# MAIN.net
KiCad netlist of a schematic drawn in Altium Designer
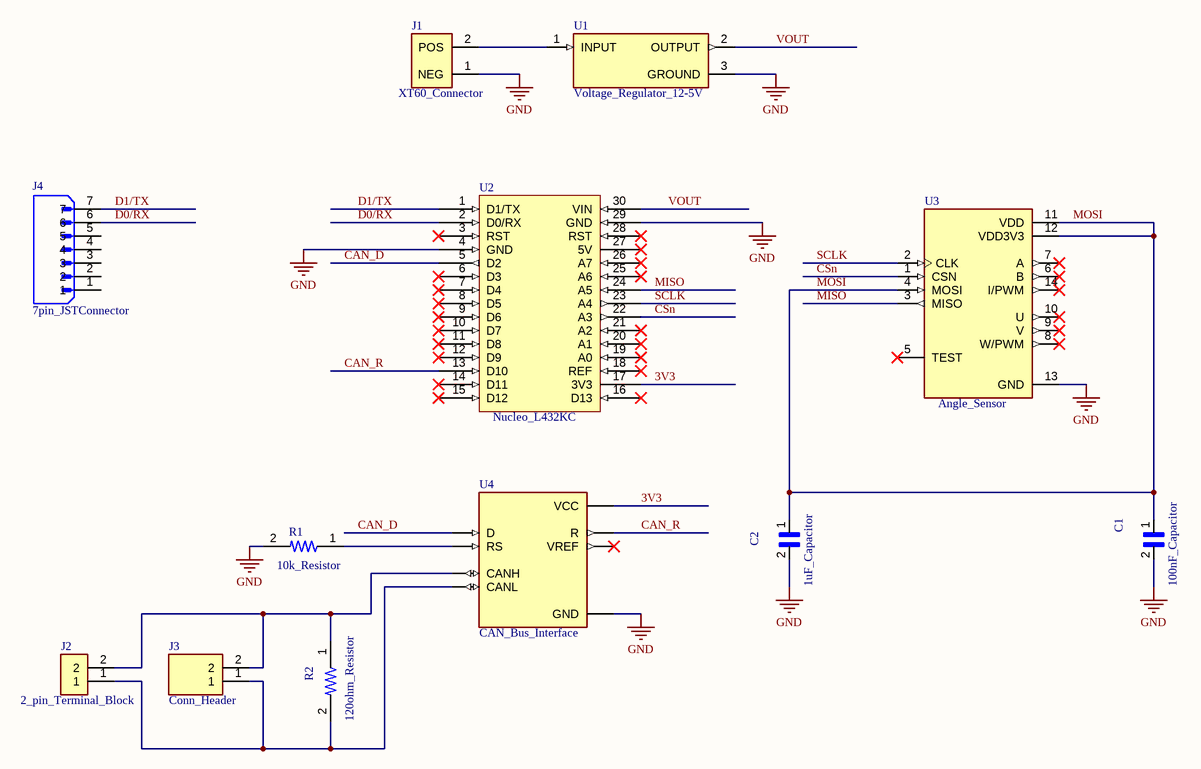
[diagram p0: MAIN.SchDoc]

(export (version "E")
  (design (tool "Eeschema 10.0.6"))
  (components
    (comp (ref "C1")
      (value "100nF_Capacitor")
      (footprint "100nF_Capacitor")
      (description "Multilayer Ceramic Capacitors MLCC - SMD/SMT 100nF 25volts 10%")
      (fields
        (field (name "MANUFACTURER") "Vishay Vitramon")
        (field (name "MANUFACTURER PART NUMBER") "VJ0603Y104KLXAC5G")
      )
      (libsource (lib "Sch_Lib") (part "100nF_Capacitor"))
    )
    (comp (ref "C2")
      (value "1uF_Capacitor")
      (footprint "1uF_Capacitor")
      (description "Multilayer Ceramic Capacitors MLCC - SMD/SMT 1uF 50V 0603 RoHS")
      (fields
        (field (name "MANUFACTURER") "Yageo")
        (field (name "MANUFACTURER PART NUMBER") "CC0603KRX5R9BB105")
      )
      (libsource (lib "Sch_Lib") (part "1uF_Capacitor"))
    )
    (comp (ref "J1")
      (value "XT60_Connector")
      (footprint "XT60_Connector")
      (description "20.5x8.1mm 铜镀金 DC500V 30A")
      (fields (field (name "MANUFACTURER") "Amass") (field (name "MANUFACTURER PART NUMBER") "XT60-M"))
      (libsource (lib "Sch_Lib") (part "XT60_Connector"))
    )
    (comp (ref "J2")
      (value "2_pin_Terminal_Block")
      (footprint "Terminal_Block")
      (description "Connector, Terminal Block; Wire Receptacle; 2 Pos.; 16-30 AWG; 0.2 in. CL; Side;")
      (fields
        (field (name "MANUFACTURER") "TE Connectivity")
        (field (name "MANUFACTURER PART NUMBER") "282837-2")
      )
      (libsource (lib "Sch_Lib") (part "2_pin_Terminal_Block"))
    )
    (comp (ref "J3")
      (value "Conn_Header")
      (footprint "Conn_Header")
      (description "Conn Unshrouded Header HDR 2 POS 2.54mm Solder ST Thru-Hole Automotive Carton")
      (fields
        (field (name "MANUFACTURER") "TE Connectivity")
        (field (name "MANUFACTURER PART NUMBER") "826629-2")
      )
      (libsource (lib "Sch_Lib") (part "Conn_Header"))
    )
    (comp (ref "J4")
      (value "7pin_JSTConnector")
      (footprint "7pin_JSTConnector")
      (description "Connector Header, XH Series, 7 Position, 2.50mm, Through Hole, Press-Fit, Solder, Natural")
      (fields
        (field (name "MANUFACTURER") "JST")
        (field (name "MANUFACTURER PART NUMBER") "B7B-XH-A(LF)(SN)")
      )
      (libsource (lib "Sch_Lib") (part "7pin_JSTConnector"))
    )
    (comp (ref "R1")
      (value "10k_Resistor")
      (footprint "10k_Resistor")
      (description "Res Thin Film 0603 10K Ohm 0.1% 0.167W ±25ppm/C Epoxy Pad SMD T/R")
      (fields
        (field (name "MANUFACTURER") "TE Connectivity")
        (field (name "MANUFACTURER PART NUMBER") "RP73PF1J10KBTDF")
      )
      (libsource (lib "Sch_Lib") (part "10k_Resistor"))
    )
    (comp (ref "R2")
      (value "120ohm_Resistor")
      (footprint "120ohm_Resistor")
      (description "Res Thick Film 0603 120 Ohm 1% 1/10W ±100ppm/°C Molded SMD SMD Paper T/R")
      (fields
        (field (name "MANUFACTURER") "Yageo")
        (field (name "MANUFACTURER PART NUMBER") "RC0603FR-10120RL")
      )
      (libsource (lib "Sch_Lib") (part "120ohm_Resistor"))
    )
    (comp (ref "U1")
      (value "Voltage_Regulator_12-5V")
      (footprint "Voltage_Regulator_12-5V")
      (description "IC REG LDO 5V 1.5A DPAK")
      (fields
        (field (name "MANUFACTURER") "STMicroelectronics")
        (field (name "MANUFACTURER PART NUMBER") "L7805CDT-TR")
      )
      (libsource (lib "Sch_Lib") (part "Voltage_Regulator_12-5V"))
    )
    (comp (ref "U2")
      (value "Nucleo_L432KC")
      (footprint "Nucleo_L432KC")
      (description "STM32 Nucleo-32 development board with STM32L432KC MCU, supports Arduino connectivity")
      (fields
        (field (name "MANUFACTURER") "STMicroelectronics")
        (field (name "MANUFACTURER PART NUMBER") "NUCLEO-L432KC")
      )
      (libsource (lib "Sch_Lib") (part "Nucleo_L432KC"))
    )
    (comp (ref "U3")
      (value "Angle_Sensor")
      (footprint "Angle_Sensor_AS5047P")
      (description "AS5047P Series 5.5 V 14-bit On-Axis Magnetic Rotary Position Sensor - TSSOP-14")
      (fields (field (name "MANUFACTURER") "ams") (field (name "MANUFACTURER PART NUMBER") "AS5047P-ATSM"))
      (libsource (lib "Sch_Lib") (part "Angle_Sensor"))
    )
    (comp (ref "U4")
      (value "CAN_Bus_Interface")
      (footprint "CAN_Bus_Interface")
      (fields
        (field (name "MANUFACTURER") "Texas Instruments")
        (field (name "MANUFACTURER PART NUMBER") "SN65HVD230")
      )
      (libsource (lib "Sch_Lib") (part "CAN_Bus_Interface"))
    )
  )
  (nets
    (net (code "1") (name "/3V3") (class "Default")
      (node (ref "U2") (pin "17") (pinfunction "3V3_17") (pintype "power_in"))
      (node (ref "U4") (pin "3") (pinfunction "VCC_3") (pintype "power_in"))
    )
    (net (code "2") (name "/CAN_D") (class "Default")
      (node (ref "U2") (pin "5") (pinfunction "D2_5") (pintype "output"))
      (node (ref "U4") (pin "1") (pinfunction "D_1") (pintype "input"))
    )
    (net (code "3") (name "/CAN_R") (class "Default")
      (node (ref "U2") (pin "13") (pinfunction "D10_13") (pintype "input"))
      (node (ref "U4") (pin "4") (pinfunction "R_4") (pintype "output"))
    )
    (net (code "4") (name "/CSn") (class "Default")
      (node (ref "U2") (pin "22") (pinfunction "A3_22") (pintype "output"))
      (node (ref "U3") (pin "1") (pinfunction "CSN_1") (pintype "input"))
    )
    (net (code "5") (name "/D0{slash}RX") (class "Default")
      (node (ref "J4") (pin "6") (pinfunction "6_6") (pintype "passive"))
      (node (ref "U2") (pin "2") (pinfunction "D0/RX_2") (pintype "input"))
    )
    (net (code "6") (name "/D1{slash}TX") (class "Default")
      (node (ref "J4") (pin "7") (pinfunction "7_7") (pintype "passive"))
      (node (ref "U2") (pin "1") (pinfunction "D1/TX_1") (pintype "input"))
    )
    (net (code "7") (name "/MISO") (class "Default")
      (node (ref "U2") (pin "24") (pinfunction "A5_24") (pintype "input"))
      (node (ref "U3") (pin "3") (pinfunction "MISO_3") (pintype "output"))
    )
    (net (code "8") (name "/MOSI") (class "Default")
      (node (ref "C1") (pin "1") (pinfunction "1_1") (pintype "passive"))
      (node (ref "C2") (pin "1") (pinfunction "1_1") (pintype "passive"))
      (node (ref "U3") (pin "11") (pinfunction "VDD_11") (pintype "power_in"))
      (node (ref "U3") (pin "12") (pinfunction "VDD3V3_12") (pintype "power_in"))
      (node (ref "U3") (pin "4") (pinfunction "MOSI_4") (pintype "input"))
    )
    (net (code "9") (name "/SCLK") (class "Default")
      (node (ref "U2") (pin "23") (pinfunction "A4_23") (pintype "output"))
      (node (ref "U3") (pin "2") (pinfunction "CLK_2") (pintype "input"))
    )
    (net (code "10") (name "/VOUT") (class "Default")
      (node (ref "U1") (pin "2") (pinfunction "OUTPUT_2") (pintype "output"))
      (node (ref "U2") (pin "30") (pinfunction "VIN_30") (pintype "input"))
    )
    (net (code "11") (name "GND") (class "Default")
      (node (ref "C1") (pin "2") (pinfunction "2_2") (pintype "passive"))
      (node (ref "C2") (pin "2") (pinfunction "2_2") (pintype "passive"))
      (node (ref "J1") (pin "1") (pinfunction "NEG_1") (pintype "passive"))
      (node (ref "R1") (pin "2") (pinfunction "2_2") (pintype "passive"))
      (node (ref "U1") (pin "3") (pinfunction "GROUND_3") (pintype "power_in"))
      (node (ref "U2") (pin "29") (pinfunction "GND_29") (pintype "input"))
      (node (ref "U2") (pin "4") (pinfunction "GND_4") (pintype "input"))
      (node (ref "U3") (pin "13") (pinfunction "GND_13") (pintype "power_in"))
      (node (ref "U4") (pin "2") (pinfunction "GND_2") (pintype "power_in"))
    )
    (net (code "12") (name "Net-(J1-POS)") (class "Default")
      (node (ref "J1") (pin "2") (pinfunction "POS_2") (pintype "passive"))
      (node (ref "U1") (pin "1") (pinfunction "INPUT_1") (pintype "input"))
    )
    (net (code "13") (name "Net-(U4-CANH)") (class "Default")
      (node (ref "J2") (pin "2") (pinfunction "2_2") (pintype "passive"))
      (node (ref "J3") (pin "2") (pinfunction "2_2") (pintype "passive"))
      (node (ref "R2") (pin "1") (pinfunction "1_1") (pintype "passive"))
      (node (ref "U4") (pin "7") (pinfunction "CANH_7") (pintype "bidirectional"))
    )
    (net (code "14") (name "Net-(U4-CANL)") (class "Default")
      (node (ref "J2") (pin "1") (pinfunction "1_1") (pintype "passive"))
      (node (ref "J3") (pin "1") (pinfunction "1_1") (pintype "passive"))
      (node (ref "R2") (pin "2") (pinfunction "2_2") (pintype "passive"))
      (node (ref "U4") (pin "6") (pinfunction "CANL_6") (pintype "bidirectional"))
    )
    (net (code "15") (name "Net-(U4-RS)") (class "Default")
      (node (ref "R1") (pin "1") (pinfunction "1_1") (pintype "passive"))
      (node (ref "U4") (pin "8") (pinfunction "RS_8") (pintype "input"))
    )
    (net (code "16") (name "unconnected-(J4-Pad1)") (class "Default")
      (node (ref "J4") (pin "1") (pinfunction "1_1") (pintype "passive"))
    )
    (net (code "17") (name "unconnected-(J4-Pad2)") (class "Default")
      (node (ref "J4") (pin "2") (pinfunction "2_2") (pintype "passive"))
    )
    (net (code "18") (name "unconnected-(J4-Pad3)") (class "Default")
      (node (ref "J4") (pin "3") (pinfunction "3_3") (pintype "passive"))
    )
    (net (code "19") (name "unconnected-(J4-Pad4)") (class "Default")
      (node (ref "J4") (pin "4") (pinfunction "4_4") (pintype "passive"))
    )
    (net (code "20") (name "unconnected-(J4-Pad5)") (class "Default")
      (node (ref "J4") (pin "5") (pinfunction "5_5") (pintype "passive"))
    )
    (net (code "21") (name "unconnected-(U2-5V-Pad27)") (class "Default")
      (node (ref "U2") (pin "27") (pinfunction "5V_27") (pintype "power_in+no_connect"))
    )
    (net (code "22") (name "unconnected-(U2-A0-Pad19)") (class "Default")
      (node (ref "U2") (pin "19") (pinfunction "A0_19") (pintype "input+no_connect"))
    )
    (net (code "23") (name "unconnected-(U2-A1-Pad20)") (class "Default")
      (node (ref "U2") (pin "20") (pinfunction "A1_20") (pintype "input+no_connect"))
    )
    (net (code "24") (name "unconnected-(U2-A2-Pad21)") (class "Default")
      (node (ref "U2") (pin "21") (pinfunction "A2_21") (pintype "input+no_connect"))
    )
    (net (code "25") (name "unconnected-(U2-A6-Pad25)") (class "Default")
      (node (ref "U2") (pin "25") (pinfunction "A6_25") (pintype "input+no_connect"))
    )
    (net (code "26") (name "unconnected-(U2-A7-Pad26)") (class "Default")
      (node (ref "U2") (pin "26") (pinfunction "A7_26") (pintype "input+no_connect"))
    )
    (net (code "27") (name "unconnected-(U2-D3-Pad6)") (class "Default")
      (node (ref "U2") (pin "6") (pinfunction "D3_6") (pintype "input+no_connect"))
    )
    (net (code "28") (name "unconnected-(U2-D4-Pad7)") (class "Default")
      (node (ref "U2") (pin "7") (pinfunction "D4_7") (pintype "input+no_connect"))
    )
    (net (code "29") (name "unconnected-(U2-D5-Pad8)") (class "Default")
      (node (ref "U2") (pin "8") (pinfunction "D5_8") (pintype "input+no_connect"))
    )
    (net (code "30") (name "unconnected-(U2-D6-Pad9)") (class "Default")
      (node (ref "U2") (pin "9") (pinfunction "D6_9") (pintype "input+no_connect"))
    )
    (net (code "31") (name "unconnected-(U2-D7-Pad10)") (class "Default")
      (node (ref "U2") (pin "10") (pinfunction "D7_10") (pintype "input+no_connect"))
    )
    (net (code "32") (name "unconnected-(U2-D8-Pad11)") (class "Default")
      (node (ref "U2") (pin "11") (pinfunction "D8_11") (pintype "input+no_connect"))
    )
    (net (code "33") (name "unconnected-(U2-D9-Pad12)") (class "Default")
      (node (ref "U2") (pin "12") (pinfunction "D9_12") (pintype "input+no_connect"))
    )
    (net (code "34") (name "unconnected-(U2-D11-Pad14)") (class "Default")
      (node (ref "U2") (pin "14") (pinfunction "D11_14") (pintype "input+no_connect"))
    )
    (net (code "35") (name "unconnected-(U2-D12-Pad15)") (class "Default")
      (node (ref "U2") (pin "15") (pinfunction "D12_15") (pintype "input+no_connect"))
    )
    (net (code "36") (name "unconnected-(U2-D13-Pad16)") (class "Default")
      (node (ref "U2") (pin "16") (pinfunction "D13_16") (pintype "input+no_connect"))
    )
    (net (code "37") (name "unconnected-(U2-REF-Pad18)") (class "Default")
      (node (ref "U2") (pin "18") (pinfunction "REF_18") (pintype "input+no_connect"))
    )
    (net (code "38") (name "unconnected-(U2-RST-Pad3)") (class "Default")
      (node (ref "U2") (pin "3") (pinfunction "RST_3") (pintype "input+no_connect"))
    )
    (net (code "39") (name "unconnected-(U2-RST-Pad28)") (class "Default")
      (node (ref "U2") (pin "28") (pinfunction "RST_28") (pintype "input+no_connect"))
    )
    (net (code "40") (name "unconnected-(U3-A-Pad7)") (class "Default")
      (node (ref "U3") (pin "7") (pinfunction "A_7") (pintype "output+no_connect"))
    )
    (net (code "41") (name "unconnected-(U3-B-Pad6)") (class "Default")
      (node (ref "U3") (pin "6") (pinfunction "B_6") (pintype "output+no_connect"))
    )
    (net (code "42") (name "unconnected-(U3-I{slash}PWM-Pad14)") (class "Default")
      (node (ref "U3") (pin "14") (pinfunction "I/PWM_14") (pintype "output+no_connect"))
    )
    (net (code "43") (name "unconnected-(U3-TEST-Pad5)") (class "Default")
      (node (ref "U3") (pin "5") (pinfunction "TEST_5") (pintype "passive+no_connect"))
    )
    (net (code "44") (name "unconnected-(U3-U-Pad10)") (class "Default")
      (node (ref "U3") (pin "10") (pinfunction "U_10") (pintype "output+no_connect"))
    )
    (net (code "45") (name "unconnected-(U3-V-Pad9)") (class "Default")
      (node (ref "U3") (pin "9") (pinfunction "V_9") (pintype "output+no_connect"))
    )
    (net (code "46") (name "unconnected-(U3-W{slash}PWM-Pad8)") (class "Default")
      (node (ref "U3") (pin "8") (pinfunction "W/PWM_8") (pintype "output+no_connect"))
    )
    (net (code "47") (name "unconnected-(U4-VREF-Pad5)") (class "Default")
      (node (ref "U4") (pin "5") (pinfunction "VREF_5") (pintype "output+no_connect"))
    )
  )
)
